# LightSensors.net
KiCad netlist of a schematic drawn in Altium Designer
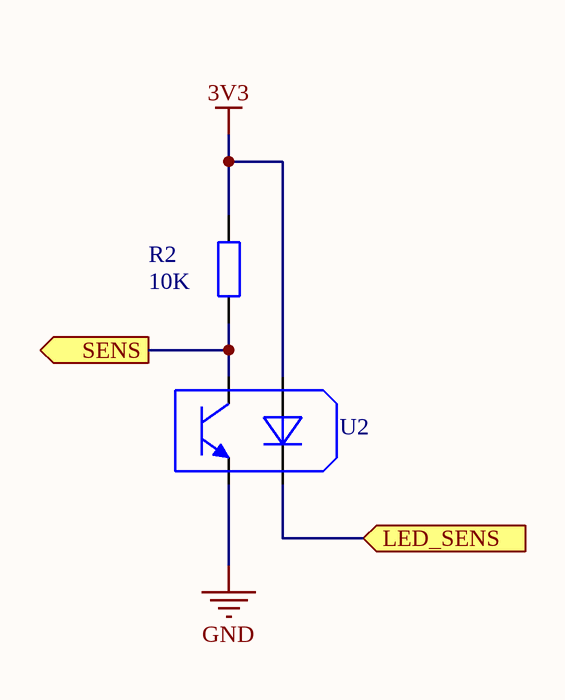
[diagram p0: LightSensors.SchDoc]

(export (version "E")
  (design (tool "Eeschema 10.0.6"))
  (components
    (comp (ref "R2")
      (value "10K")
      (footprint "FP_0805_RES")
      (description "Resistor")
      (fields (field (name "TOLERANCE") "5%") (field (name "POWER") "125mW"))
      (libsource (lib "hallglib") (part "RES 10K"))
    )
    (comp (ref "U2")
      (value "TCRT5000")
      (footprint "TCRT5000_NO_HOLE")
      (description "Reflective Photo Interrupter, Phototransistor, Through Hole, 15 mm, 60 mA, 5 Vr, 1.25 Vf")
      (libsource (lib "RobonAUT") (part "TCRT5000"))
    )
  )
  (nets
    (net (code "1") (name "/LED_SENS") (class "Default")
      (node (ref "U2") (pin "K") (pinfunction "K_K") (pintype "passive"))
    )
    (net (code "2") (name "/SENS") (class "Default")
      (node (ref "R2") (pin "1") (pinfunction "1_1") (pintype "passive"))
      (node (ref "U2") (pin "C") (pinfunction "C_C") (pintype "passive"))
    )
    (net (code "3") (name "3V3") (class "Default")
      (node (ref "R2") (pin "2") (pinfunction "2_2") (pintype "passive"))
      (node (ref "U2") (pin "A") (pinfunction "A_A") (pintype "passive"))
    )
    (net (code "4") (name "GND") (class "Default")
      (node (ref "U2") (pin "E") (pinfunction "E_E") (pintype "passive"))
    )
  )
)
